# rgb_sensor.net
KiCad netlist of a schematic drawn in EAGLE
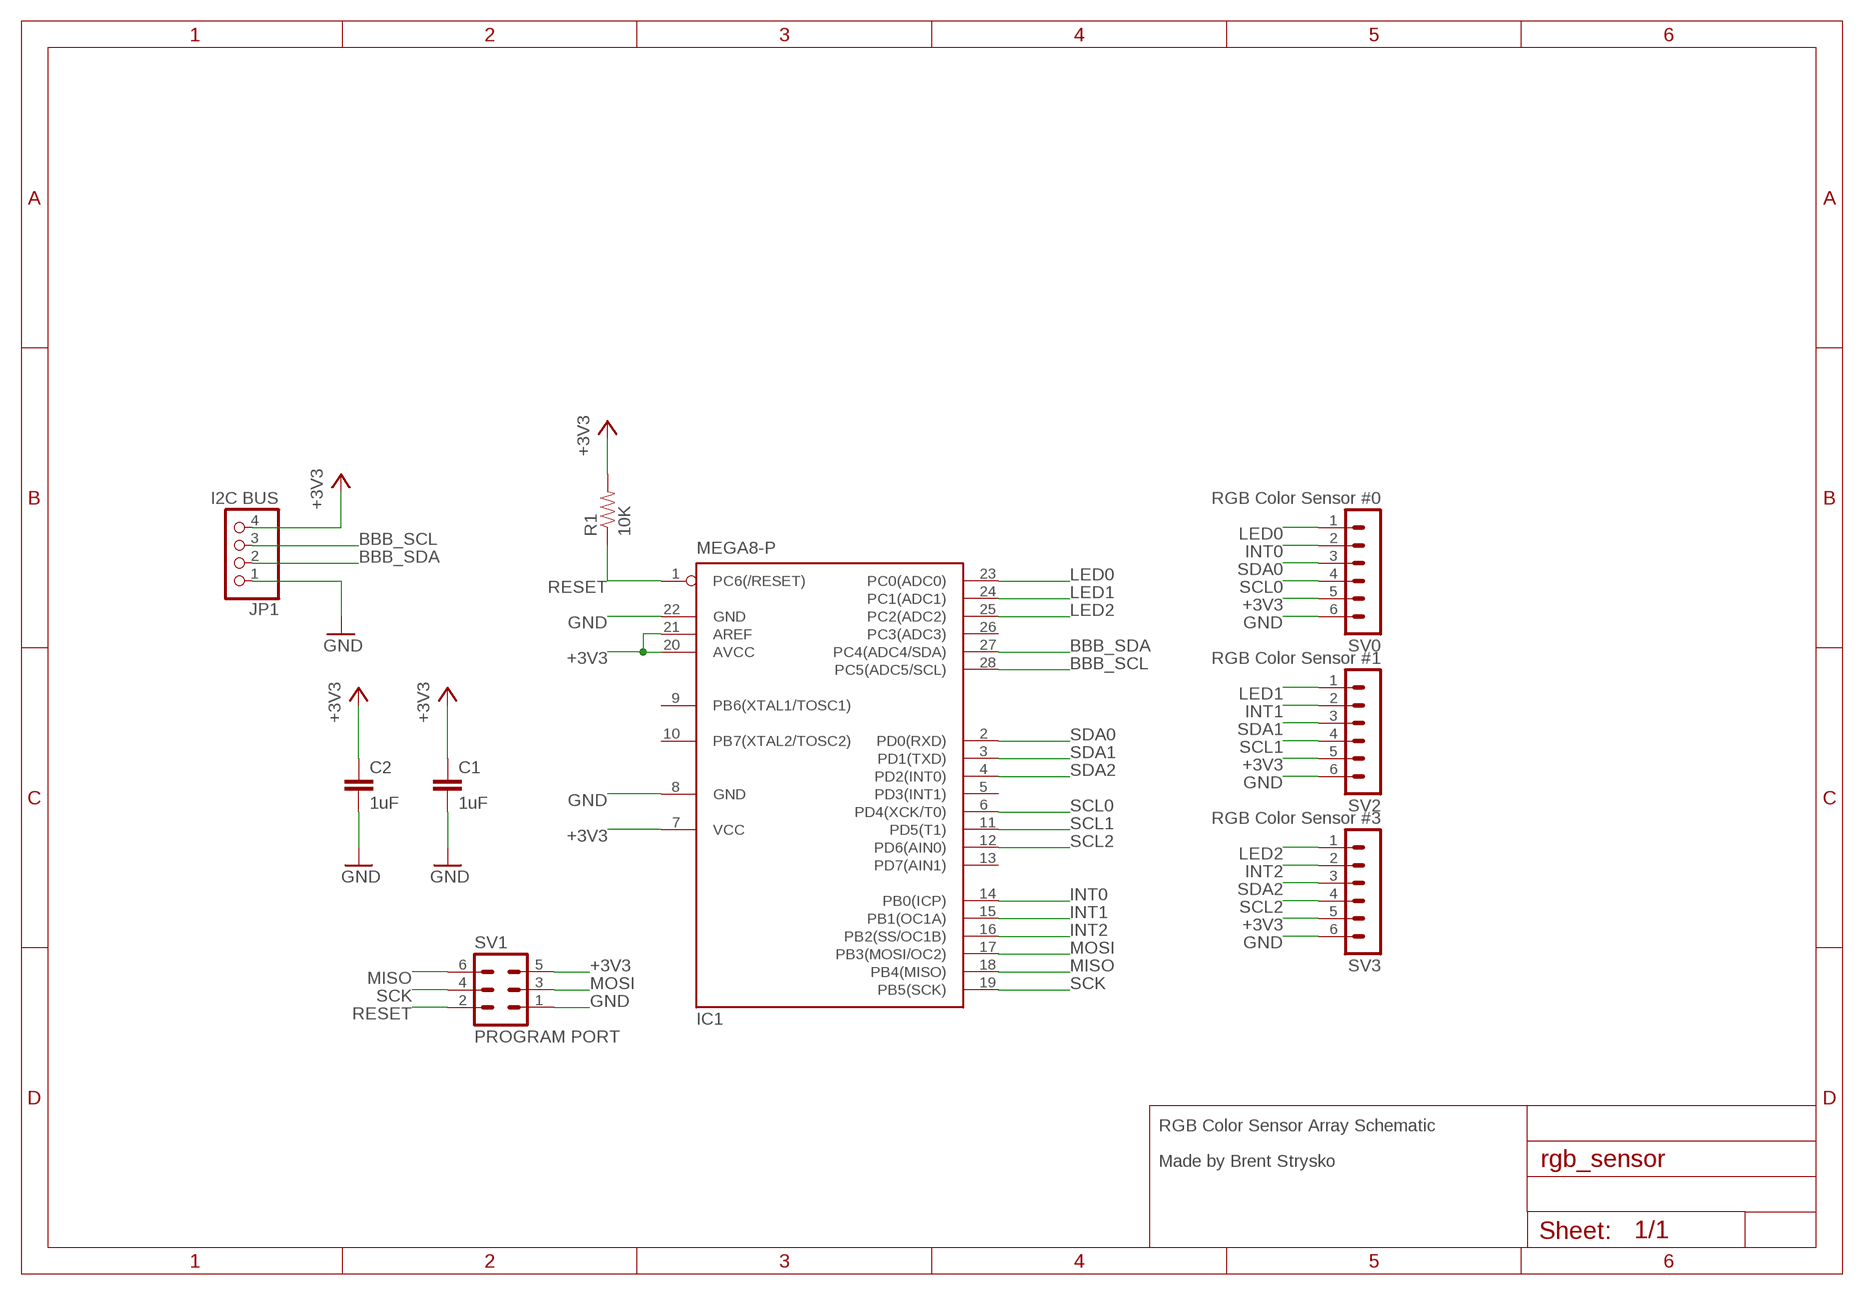
[diagram p0: schematic, sheet 1]

(export (version "E")
  (design (tool "Eeschema 10.0.6"))
  (components
    (comp (ref "C1")
      (value "1uF")
      (footprint "eagle-import:CAP-PTH-SMALL-KIT")
      (libsource (lib "eagle-import") (part "CAPKIT"))
    )
    (comp (ref "C2")
      (value "1uF")
      (footprint "eagle-import:CAP-PTH-SMALL-KIT")
      (libsource (lib "eagle-import") (part "CAPKIT"))
    )
    (comp (ref "IC1")
      (value "MEGA8-P")
      (footprint "eagle-import:DIL28-3")
      (libsource (lib "eagle-import") (part "MEGA8-P"))
    )
    (comp (ref "JP1")
      (value "I2C BUS")
      (footprint "eagle-import:1X04")
      (libsource (lib "eagle-import") (part "PINHD-1X4"))
    )
    (comp (ref "R1")
      (value "10K")
      (footprint "eagle-import:AXIAL-0.4")
      (libsource (lib "eagle-import") (part "RESISTORPTH-1/4W"))
    )
    (comp (ref "SV0")
      (value "RGB Color Sensor #0")
      (footprint "eagle-import:MA06-1")
      (libsource (lib "eagle-import") (part "MA06-1"))
    )
    (comp (ref "SV1")
      (value "PROGRAM PORT")
      (footprint "eagle-import:MA03-2")
      (libsource (lib "eagle-import") (part "MA03-2"))
    )
    (comp (ref "SV2")
      (value "RGB Color Sensor #1")
      (footprint "eagle-import:MA06-1")
      (libsource (lib "eagle-import") (part "MA06-1"))
    )
    (comp (ref "SV3")
      (value "RGB Color Sensor #3")
      (footprint "eagle-import:MA06-1")
      (libsource (lib "eagle-import") (part "MA06-1"))
    )
  )
  (nets
    (net (code "1") (name "+3V3") (class "Default")
      (node (ref "C1") (pin "1") (pinfunction "1_1") (pintype "passive"))
      (node (ref "C2") (pin "1") (pinfunction "1_1") (pintype "passive"))
      (node (ref "IC1") (pin "20") (pinfunction "AVCC_20") (pintype "power_in"))
      (node (ref "IC1") (pin "21") (pinfunction "AREF_21") (pintype "passive"))
      (node (ref "IC1") (pin "7") (pinfunction "VCC_7") (pintype "power_in"))
      (node (ref "JP1") (pin "4") (pinfunction "4_4") (pintype "passive"))
      (node (ref "R1") (pin "P$2") (pinfunction "2_P$2") (pintype "passive"))
      (node (ref "SV0") (pin "5") (pinfunction "5_5") (pintype "passive"))
      (node (ref "SV1") (pin "5") (pinfunction "5_5") (pintype "passive"))
      (node (ref "SV2") (pin "5") (pinfunction "5_5") (pintype "passive"))
      (node (ref "SV3") (pin "5") (pinfunction "5_5") (pintype "passive"))
    )
    (net (code "2") (name "/BBB_SCL") (class "Default")
      (node (ref "IC1") (pin "28") (pinfunction "PC5(ADC5/SCL)_28") (pintype "bidirectional"))
      (node (ref "JP1") (pin "3") (pinfunction "3_3") (pintype "passive"))
    )
    (net (code "3") (name "/BBB_SDA") (class "Default")
      (node (ref "IC1") (pin "27") (pinfunction "PC4(ADC4/SDA)_27") (pintype "bidirectional"))
      (node (ref "JP1") (pin "2") (pinfunction "2_2") (pintype "passive"))
    )
    (net (code "4") (name "/INT0") (class "Default")
      (node (ref "IC1") (pin "14") (pinfunction "PB0(ICP)_14") (pintype "bidirectional"))
      (node (ref "SV0") (pin "2") (pinfunction "2_2") (pintype "passive"))
    )
    (net (code "5") (name "/INT1") (class "Default")
      (node (ref "IC1") (pin "15") (pinfunction "PB1(OC1A)_15") (pintype "bidirectional"))
      (node (ref "SV2") (pin "2") (pinfunction "2_2") (pintype "passive"))
    )
    (net (code "6") (name "/INT2") (class "Default")
      (node (ref "IC1") (pin "16") (pinfunction "PB2(SS/OC1B)_16") (pintype "bidirectional"))
      (node (ref "SV3") (pin "2") (pinfunction "2_2") (pintype "passive"))
    )
    (net (code "7") (name "/LED0") (class "Default")
      (node (ref "IC1") (pin "23") (pinfunction "PC0(ADC0)_23") (pintype "bidirectional"))
      (node (ref "SV0") (pin "1") (pinfunction "1_1") (pintype "passive"))
    )
    (net (code "8") (name "/LED1") (class "Default")
      (node (ref "IC1") (pin "24") (pinfunction "PC1(ADC1)_24") (pintype "bidirectional"))
      (node (ref "SV2") (pin "1") (pinfunction "1_1") (pintype "passive"))
    )
    (net (code "9") (name "/LED2") (class "Default")
      (node (ref "IC1") (pin "25") (pinfunction "PC2(ADC2)_25") (pintype "bidirectional"))
      (node (ref "SV3") (pin "1") (pinfunction "1_1") (pintype "passive"))
    )
    (net (code "10") (name "/MISO") (class "Default")
      (node (ref "IC1") (pin "18") (pinfunction "PB4(MISO)_18") (pintype "bidirectional"))
      (node (ref "SV1") (pin "6") (pinfunction "6_6") (pintype "passive"))
    )
    (net (code "11") (name "/MOSI") (class "Default")
      (node (ref "IC1") (pin "17") (pinfunction "PB3(MOSI/OC2)_17") (pintype "bidirectional"))
      (node (ref "SV1") (pin "3") (pinfunction "3_3") (pintype "passive"))
    )
    (net (code "12") (name "/RESET") (class "Default")
      (node (ref "IC1") (pin "1") (pinfunction "PC6(/RESET)_1") (pintype "bidirectional"))
      (node (ref "R1") (pin "P$1") (pinfunction "1_P$1") (pintype "passive"))
      (node (ref "SV1") (pin "2") (pinfunction "2_2") (pintype "passive"))
    )
    (net (code "13") (name "/SCK") (class "Default")
      (node (ref "IC1") (pin "19") (pinfunction "PB5(SCK)_19") (pintype "bidirectional"))
      (node (ref "SV1") (pin "4") (pinfunction "4_4") (pintype "passive"))
    )
    (net (code "14") (name "/SCL0") (class "Default")
      (node (ref "IC1") (pin "6") (pinfunction "PD4(XCK/T0)_6") (pintype "bidirectional"))
      (node (ref "SV0") (pin "4") (pinfunction "4_4") (pintype "passive"))
    )
    (net (code "15") (name "/SCL1") (class "Default")
      (node (ref "IC1") (pin "11") (pinfunction "PD5(T1)_11") (pintype "bidirectional"))
      (node (ref "SV2") (pin "4") (pinfunction "4_4") (pintype "passive"))
    )
    (net (code "16") (name "/SCL2") (class "Default")
      (node (ref "IC1") (pin "12") (pinfunction "PD6(AIN0)_12") (pintype "bidirectional"))
      (node (ref "SV3") (pin "4") (pinfunction "4_4") (pintype "passive"))
    )
    (net (code "17") (name "/SDA0") (class "Default")
      (node (ref "IC1") (pin "2") (pinfunction "PD0(RXD)_2") (pintype "bidirectional"))
      (node (ref "SV0") (pin "3") (pinfunction "3_3") (pintype "passive"))
    )
    (net (code "18") (name "/SDA1") (class "Default")
      (node (ref "IC1") (pin "3") (pinfunction "PD1(TXD)_3") (pintype "bidirectional"))
      (node (ref "SV2") (pin "3") (pinfunction "3_3") (pintype "passive"))
    )
    (net (code "19") (name "/SDA2") (class "Default")
      (node (ref "IC1") (pin "4") (pinfunction "PD2(INT0)_4") (pintype "bidirectional"))
      (node (ref "SV3") (pin "3") (pinfunction "3_3") (pintype "passive"))
    )
    (net (code "20") (name "GND") (class "Default")
      (node (ref "C1") (pin "2") (pinfunction "2_2") (pintype "passive"))
      (node (ref "C2") (pin "2") (pinfunction "2_2") (pintype "passive"))
      (node (ref "IC1") (pin "22") (pinfunction "GND_22") (pintype "power_in"))
      (node (ref "IC1") (pin "8") (pinfunction "GND_8") (pintype "power_in"))
      (node (ref "JP1") (pin "1") (pinfunction "1_1") (pintype "passive"))
      (node (ref "SV0") (pin "6") (pinfunction "6_6") (pintype "passive"))
      (node (ref "SV1") (pin "1") (pinfunction "1_1") (pintype "passive"))
      (node (ref "SV2") (pin "6") (pinfunction "6_6") (pintype "passive"))
      (node (ref "SV3") (pin "6") (pinfunction "6_6") (pintype "passive"))
    )
    (net (code "21") (name "unconnected-(IC1-PB6(XTAL1{slash}TOSC1)-Pad9)") (class "Default")
      (node (ref "IC1") (pin "9") (pinfunction "PB6(XTAL1/TOSC1)_9") (pintype "bidirectional"))
    )
    (net (code "22") (name "unconnected-(IC1-PB7(XTAL2{slash}TOSC2)-Pad10)") (class "Default")
      (node (ref "IC1") (pin "10") (pinfunction "PB7(XTAL2/TOSC2)_10") (pintype "bidirectional"))
    )
    (net (code "23") (name "unconnected-(IC1-PC3(ADC3)-Pad26)") (class "Default")
      (node (ref "IC1") (pin "26") (pinfunction "PC3(ADC3)_26") (pintype "bidirectional"))
    )
    (net (code "24") (name "unconnected-(IC1-PD3(INT1)-Pad5)") (class "Default")
      (node (ref "IC1") (pin "5") (pinfunction "PD3(INT1)_5") (pintype "bidirectional"))
    )
    (net (code "25") (name "unconnected-(IC1-PD7(AIN1)-Pad13)") (class "Default")
      (node (ref "IC1") (pin "13") (pinfunction "PD7(AIN1)_13") (pintype "bidirectional"))
    )
  )
)
